# PWM_Isolated.net
KiCad netlist of a schematic drawn in Altium Designer
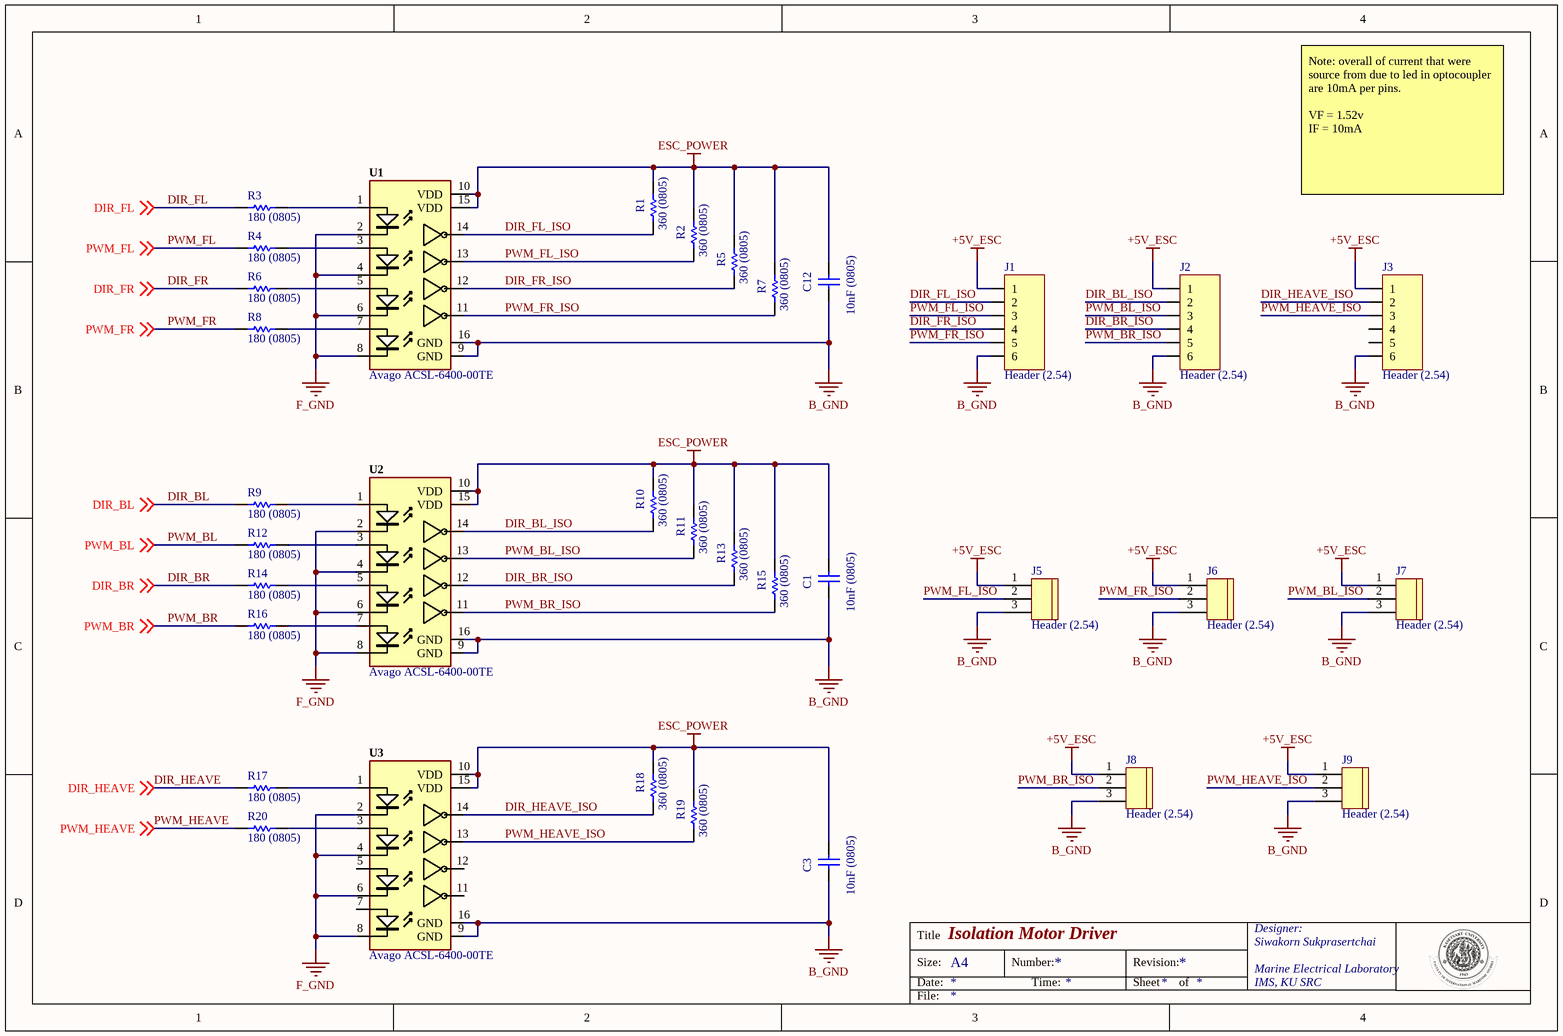
[diagram p0: PWM_Isolated.SchDoc]

(export (version "E")
  (design (tool "Eeschema 10.0.6"))
  (components
    (comp (ref "C1")
      (value "10nF (0805)")
      (footprint "CAPC2013X94X50NL20T25")
      (description "CAP CER 10NF 50V 5% X7R 0805")
      (fields (field (name "MANUFACTURER PART NUMBER") "08055C103JAT2A"))
      (libsource (lib "FavoritesLibrary") (part "CAP-2"))
    )
    (comp (ref "C3")
      (value "10nF (0805)")
      (footprint "CAPC2013X94X50NL20T25")
      (description "CAP CER 10NF 50V 5% X7R 0805")
      (fields (field (name "MANUFACTURER PART NUMBER") "08055C103JAT2A"))
      (libsource (lib "FavoritesLibrary") (part "CAP-2"))
    )
    (comp (ref "C12")
      (value "10nF (0805)")
      (footprint "CAPC2013X94X50NL20T25")
      (description "CAP CER 10NF 50V 5% X7R 0805")
      (fields (field (name "MANUFACTURER PART NUMBER") "08055C103JAT2A"))
      (libsource (lib "FavoritesLibrary") (part "CAP-2"))
    )
    (comp (ref "J1")
      (value "Header (2.54)")
      (footprint "PCB-cqg2o6bffgevoirlg0wu-1")
      (description "Wire-To-Board Connector, Right Angle, AMPMODU Mod II Series, Through Hole, Header, 6, 2.54 mm")
      (fields (field (name "MANUFACTURER PART NUMBER") "826947-6"))
      (libsource (lib "CommunityVault") (part "CMP-c0620b0c5e311fa5-2"))
    )
    (comp (ref "J2")
      (value "Header (2.54)")
      (footprint "PCB-cqg2o6bffgevoirlg0wu-1")
      (description "Wire-To-Board Connector, Right Angle, AMPMODU Mod II Series, Through Hole, Header, 6, 2.54 mm")
      (fields (field (name "MANUFACTURER PART NUMBER") "826947-6"))
      (libsource (lib "CommunityVault") (part "CMP-c0620b0c5e311fa5-2"))
    )
    (comp (ref "J3")
      (value "Header (2.54)")
      (footprint "PCB-cqg2o6bffgevoirlg0wu-1")
      (description "Wire-To-Board Connector, Right Angle, AMPMODU Mod II Series, Through Hole, Header, 6, 2.54 mm")
      (fields (field (name "MANUFACTURER PART NUMBER") "826947-6"))
      (libsource (lib "CommunityVault") (part "CMP-c0620b0c5e311fa5-2"))
    )
    (comp (ref "J5")
      (value "Header (2.54)")
      (footprint "PCB-euxx5fdf5mehbg45u1ir-1")
      (description "Pin strip (standard) MTA-100 Total number of pins 3 TE Connectivity 640455-3 1 pc(s)")
      (fields (field (name "MANUFACTURER PART NUMBER") "640455-3"))
      (libsource (lib "CommunityVault") (part "CMP-b27b7b724c836dbc-1"))
    )
    (comp (ref "J6")
      (value "Header (2.54)")
      (footprint "PCB-euxx5fdf5mehbg45u1ir-1")
      (description "Pin strip (standard) MTA-100 Total number of pins 3 TE Connectivity 640455-3 1 pc(s)")
      (fields (field (name "MANUFACTURER PART NUMBER") "640455-3"))
      (libsource (lib "CommunityVault") (part "CMP-b27b7b724c836dbc-1"))
    )
    (comp (ref "J7")
      (value "Header (2.54)")
      (footprint "PCB-euxx5fdf5mehbg45u1ir-1")
      (description "Pin strip (standard) MTA-100 Total number of pins 3 TE Connectivity 640455-3 1 pc(s)")
      (fields (field (name "MANUFACTURER PART NUMBER") "640455-3"))
      (libsource (lib "CommunityVault") (part "CMP-b27b7b724c836dbc-1"))
    )
    (comp (ref "J8")
      (value "Header (2.54)")
      (footprint "PCB-euxx5fdf5mehbg45u1ir-1")
      (description "Pin strip (standard) MTA-100 Total number of pins 3 TE Connectivity 640455-3 1 pc(s)")
      (fields (field (name "MANUFACTURER PART NUMBER") "640455-3"))
      (libsource (lib "CommunityVault") (part "CMP-b27b7b724c836dbc-1"))
    )
    (comp (ref "J9")
      (value "Header (2.54)")
      (footprint "PCB-euxx5fdf5mehbg45u1ir-1")
      (description "Pin strip (standard) MTA-100 Total number of pins 3 TE Connectivity 640455-3 1 pc(s)")
      (fields (field (name "MANUFACTURER PART NUMBER") "640455-3"))
      (libsource (lib "CommunityVault") (part "CMP-b27b7b724c836dbc-1"))
    )
    (comp (ref "R1")
      (value "360 (0805)")
      (footprint "RESC2013X60X40NL15T20")
      (description "RES SMD 10K OHM 1% 1/3W 0805")
      (libsource (lib "CommunityVault") (part "CMP-1860549-2"))
    )
    (comp (ref "R2")
      (value "360 (0805)")
      (footprint "RESC2013X60X40NL15T20")
      (description "RES SMD 10K OHM 1% 1/3W 0805")
      (libsource (lib "CommunityVault") (part "CMP-1860549-2"))
    )
    (comp (ref "R3")
      (value "180 (0805)")
      (footprint "RESC2013X60X40NL15T20")
      (description "RES SMD 10K OHM 1% 1/3W 0805")
      (libsource (lib "FavoritesLibrary") (part "RES-2"))
    )
    (comp (ref "R4")
      (value "180 (0805)")
      (footprint "RESC2013X60X40NL15T20")
      (description "RES SMD 10K OHM 1% 1/3W 0805")
      (libsource (lib "FavoritesLibrary") (part "RES-2"))
    )
    (comp (ref "R5")
      (value "360 (0805)")
      (footprint "RESC2013X60X40NL15T20")
      (description "RES SMD 10K OHM 1% 1/3W 0805")
      (libsource (lib "CommunityVault") (part "CMP-1860549-2"))
    )
    (comp (ref "R6")
      (value "180 (0805)")
      (footprint "RESC2013X60X40NL15T20")
      (description "RES SMD 10K OHM 1% 1/3W 0805")
      (libsource (lib "FavoritesLibrary") (part "RES-2"))
    )
    (comp (ref "R7")
      (value "360 (0805)")
      (footprint "RESC2013X60X40NL15T20")
      (description "RES SMD 10K OHM 1% 1/3W 0805")
      (libsource (lib "CommunityVault") (part "CMP-1860549-2"))
    )
    (comp (ref "R8")
      (value "180 (0805)")
      (footprint "RESC2013X60X40NL15T20")
      (description "RES SMD 10K OHM 1% 1/3W 0805")
      (libsource (lib "FavoritesLibrary") (part "RES-2"))
    )
    (comp (ref "R9")
      (value "180 (0805)")
      (footprint "RESC2013X60X40NL15T20")
      (description "RES SMD 10K OHM 1% 1/3W 0805")
      (libsource (lib "FavoritesLibrary") (part "RES-2"))
    )
    (comp (ref "R10")
      (value "360 (0805)")
      (footprint "RESC2013X60X40NL15T20")
      (description "RES SMD 10K OHM 1% 1/3W 0805")
      (libsource (lib "CommunityVault") (part "CMP-1860549-2"))
    )
    (comp (ref "R11")
      (value "360 (0805)")
      (footprint "RESC2013X60X40NL15T20")
      (description "RES SMD 10K OHM 1% 1/3W 0805")
      (libsource (lib "CommunityVault") (part "CMP-1860549-2"))
    )
    (comp (ref "R12")
      (value "180 (0805)")
      (footprint "RESC2013X60X40NL15T20")
      (description "RES SMD 10K OHM 1% 1/3W 0805")
      (libsource (lib "FavoritesLibrary") (part "RES-2"))
    )
    (comp (ref "R13")
      (value "360 (0805)")
      (footprint "RESC2013X60X40NL15T20")
      (description "RES SMD 10K OHM 1% 1/3W 0805")
      (libsource (lib "CommunityVault") (part "CMP-1860549-2"))
    )
    (comp (ref "R14")
      (value "180 (0805)")
      (footprint "RESC2013X60X40NL15T20")
      (description "RES SMD 10K OHM 1% 1/3W 0805")
      (libsource (lib "FavoritesLibrary") (part "RES-2"))
    )
    (comp (ref "R15")
      (value "360 (0805)")
      (footprint "RESC2013X60X40NL15T20")
      (description "RES SMD 10K OHM 1% 1/3W 0805")
      (libsource (lib "CommunityVault") (part "CMP-1860549-2"))
    )
    (comp (ref "R16")
      (value "180 (0805)")
      (footprint "RESC2013X60X40NL15T20")
      (description "RES SMD 10K OHM 1% 1/3W 0805")
      (libsource (lib "FavoritesLibrary") (part "RES-2"))
    )
    (comp (ref "R17")
      (value "180 (0805)")
      (footprint "RESC2013X60X40NL15T20")
      (description "RES SMD 10K OHM 1% 1/3W 0805")
      (libsource (lib "FavoritesLibrary") (part "RES-2"))
    )
    (comp (ref "R18")
      (value "360 (0805)")
      (footprint "RESC2013X60X40NL15T20")
      (description "RES SMD 10K OHM 1% 1/3W 0805")
      (libsource (lib "CommunityVault") (part "CMP-1860549-2"))
    )
    (comp (ref "R19")
      (value "360 (0805)")
      (footprint "RESC2013X60X40NL15T20")
      (description "RES SMD 10K OHM 1% 1/3W 0805")
      (libsource (lib "CommunityVault") (part "CMP-1860549-2"))
    )
    (comp (ref "R20")
      (value "180 (0805)")
      (footprint "RESC2013X60X40NL15T20")
      (description "RES SMD 10K OHM 1% 1/3W 0805")
      (libsource (lib "FavoritesLibrary") (part "RES-2"))
    )
    (comp (ref "U1")
      (value "Avago ACSL-6400-00TE")
      (footprint "PCB-bbpchabnk3r0s5lan1zs-1")
      (description "Multi-Channel and Bi-Directional, 15 MBd (typ) Digital Logic Gate Optocoupler")
      (fields (field (name "MANUFACTURER PART NUMBER") "ACSL-6400-00TE"))
      (libsource (lib "FavoritesLibrary") (part "SYM-6f44a640fcefb083-1"))
    )
    (comp (ref "U2")
      (value "Avago ACSL-6400-00TE")
      (footprint "PCB-bbpchabnk3r0s5lan1zs-1")
      (description "Multi-Channel and Bi-Directional, 15 MBd (typ) Digital Logic Gate Optocoupler")
      (fields (field (name "MANUFACTURER PART NUMBER") "ACSL-6400-00TE"))
      (libsource (lib "FavoritesLibrary") (part "SYM-6f44a640fcefb083-1"))
    )
    (comp (ref "U3")
      (value "Avago ACSL-6400-00TE")
      (footprint "PCB-bbpchabnk3r0s5lan1zs-1")
      (description "Multi-Channel and Bi-Directional, 15 MBd (typ) Digital Logic Gate Optocoupler")
      (fields (field (name "MANUFACTURER PART NUMBER") "ACSL-6400-00TE"))
      (libsource (lib "FavoritesLibrary") (part "SYM-6f44a640fcefb083-1"))
    )
  )
  (nets
    (net (code "1") (name "+5V_ESC") (class "Default")
      (node (ref "J1") (pin "1") (pinfunction "1_1") (pintype "passive"))
      (node (ref "J2") (pin "1") (pinfunction "1_1") (pintype "passive"))
      (node (ref "J3") (pin "1") (pinfunction "1_1") (pintype "passive"))
      (node (ref "J5") (pin "1") (pinfunction "1_1") (pintype "passive"))
      (node (ref "J6") (pin "1") (pinfunction "1_1") (pintype "passive"))
      (node (ref "J7") (pin "1") (pinfunction "1_1") (pintype "passive"))
      (node (ref "J8") (pin "1") (pinfunction "1_1") (pintype "passive"))
      (node (ref "J9") (pin "1") (pinfunction "1_1") (pintype "passive"))
    )
    (net (code "2") (name "/DIR_BL_ISO") (class "Default")
      (node (ref "J2") (pin "2") (pinfunction "2_2") (pintype "passive"))
      (node (ref "R10") (pin "2") (pinfunction "2_2") (pintype "passive"))
      (node (ref "U2") (pin "14") (pinfunction "14_14") (pintype "passive"))
    )
    (net (code "3") (name "/DIR_BR_ISO") (class "Default")
      (node (ref "J2") (pin "4") (pinfunction "4_4") (pintype "passive"))
      (node (ref "R13") (pin "2") (pinfunction "2_2") (pintype "passive"))
      (node (ref "U2") (pin "12") (pinfunction "12_12") (pintype "passive"))
    )
    (net (code "4") (name "/DIR_FL_ISO") (class "Default")
      (node (ref "J1") (pin "2") (pinfunction "2_2") (pintype "passive"))
      (node (ref "R1") (pin "2") (pinfunction "2_2") (pintype "passive"))
      (node (ref "U1") (pin "14") (pinfunction "14_14") (pintype "passive"))
    )
    (net (code "5") (name "/DIR_FR_ISO") (class "Default")
      (node (ref "J1") (pin "4") (pinfunction "4_4") (pintype "passive"))
      (node (ref "R5") (pin "2") (pinfunction "2_2") (pintype "passive"))
      (node (ref "U1") (pin "12") (pinfunction "12_12") (pintype "passive"))
    )
    (net (code "6") (name "/DIR_HEAVE_ISO") (class "Default")
      (node (ref "J3") (pin "2") (pinfunction "2_2") (pintype "passive"))
      (node (ref "R18") (pin "2") (pinfunction "2_2") (pintype "passive"))
      (node (ref "U3") (pin "14") (pinfunction "14_14") (pintype "passive"))
    )
    (net (code "7") (name "/PWM_BL_ISO") (class "Default")
      (node (ref "J2") (pin "3") (pinfunction "3_3") (pintype "passive"))
      (node (ref "J7") (pin "2") (pinfunction "2_2") (pintype "passive"))
      (node (ref "R11") (pin "2") (pinfunction "2_2") (pintype "passive"))
      (node (ref "U2") (pin "13") (pinfunction "13_13") (pintype "passive"))
    )
    (net (code "8") (name "/PWM_BR_ISO") (class "Default")
      (node (ref "J2") (pin "5") (pinfunction "5_5") (pintype "passive"))
      (node (ref "J8") (pin "2") (pinfunction "2_2") (pintype "passive"))
      (node (ref "R15") (pin "2") (pinfunction "2_2") (pintype "passive"))
      (node (ref "U2") (pin "11") (pinfunction "11_11") (pintype "passive"))
    )
    (net (code "9") (name "/PWM_FL_ISO") (class "Default")
      (node (ref "J1") (pin "3") (pinfunction "3_3") (pintype "passive"))
      (node (ref "J5") (pin "2") (pinfunction "2_2") (pintype "passive"))
      (node (ref "R2") (pin "2") (pinfunction "2_2") (pintype "passive"))
      (node (ref "U1") (pin "13") (pinfunction "13_13") (pintype "passive"))
    )
    (net (code "10") (name "/PWM_FR_ISO") (class "Default")
      (node (ref "J1") (pin "5") (pinfunction "5_5") (pintype "passive"))
      (node (ref "J6") (pin "2") (pinfunction "2_2") (pintype "passive"))
      (node (ref "R7") (pin "2") (pinfunction "2_2") (pintype "passive"))
      (node (ref "U1") (pin "11") (pinfunction "11_11") (pintype "passive"))
    )
    (net (code "11") (name "/PWM_HEAVE_ISO") (class "Default")
      (node (ref "J3") (pin "3") (pinfunction "3_3") (pintype "passive"))
      (node (ref "J9") (pin "2") (pinfunction "2_2") (pintype "passive"))
      (node (ref "R19") (pin "2") (pinfunction "2_2") (pintype "passive"))
      (node (ref "U3") (pin "13") (pinfunction "13_13") (pintype "passive"))
    )
    (net (code "12") (name "B_GND") (class "Default")
      (node (ref "C1") (pin "1") (pinfunction "1_1") (pintype "passive"))
      (node (ref "C12") (pin "1") (pinfunction "1_1") (pintype "passive"))
      (node (ref "C3") (pin "1") (pinfunction "1_1") (pintype "passive"))
      (node (ref "J1") (pin "6") (pinfunction "6_6") (pintype "passive"))
      (node (ref "J2") (pin "6") (pinfunction "6_6") (pintype "passive"))
      (node (ref "J3") (pin "6") (pinfunction "6_6") (pintype "passive"))
      (node (ref "J5") (pin "3") (pinfunction "3_3") (pintype "passive"))
      (node (ref "J6") (pin "3") (pinfunction "3_3") (pintype "passive"))
      (node (ref "J7") (pin "3") (pinfunction "3_3") (pintype "passive"))
      (node (ref "J8") (pin "3") (pinfunction "3_3") (pintype "passive"))
      (node (ref "J9") (pin "3") (pinfunction "3_3") (pintype "passive"))
      (node (ref "U1") (pin "16") (pinfunction "GND_16") (pintype "passive"))
      (node (ref "U1") (pin "9") (pinfunction "GND_9") (pintype "passive"))
      (node (ref "U2") (pin "16") (pinfunction "GND_16") (pintype "passive"))
      (node (ref "U2") (pin "9") (pinfunction "GND_9") (pintype "passive"))
      (node (ref "U3") (pin "16") (pinfunction "GND_16") (pintype "passive"))
      (node (ref "U3") (pin "9") (pinfunction "GND_9") (pintype "passive"))
    )
    (net (code "13") (name "DIR_BL") (class "Default")
      (node (ref "R9") (pin "2") (pinfunction "2_2") (pintype "passive"))
    )
    (net (code "14") (name "DIR_BR") (class "Default")
      (node (ref "R14") (pin "2") (pinfunction "2_2") (pintype "passive"))
    )
    (net (code "15") (name "DIR_FL") (class "Default")
      (node (ref "R3") (pin "2") (pinfunction "2_2") (pintype "passive"))
    )
    (net (code "16") (name "DIR_FR") (class "Default")
      (node (ref "R6") (pin "2") (pinfunction "2_2") (pintype "passive"))
    )
    (net (code "17") (name "DIR_HEAVE") (class "Default")
      (node (ref "R17") (pin "2") (pinfunction "2_2") (pintype "passive"))
    )
    (net (code "18") (name "ESC_POWER") (class "Default")
      (node (ref "C1") (pin "2") (pinfunction "2_2") (pintype "passive"))
      (node (ref "C12") (pin "2") (pinfunction "2_2") (pintype "passive"))
      (node (ref "C3") (pin "2") (pinfunction "2_2") (pintype "passive"))
      (node (ref "R1") (pin "1") (pinfunction "1_1") (pintype "passive"))
      (node (ref "R10") (pin "1") (pinfunction "1_1") (pintype "passive"))
      (node (ref "R11") (pin "1") (pinfunction "1_1") (pintype "passive"))
      (node (ref "R13") (pin "1") (pinfunction "1_1") (pintype "passive"))
      (node (ref "R15") (pin "1") (pinfunction "1_1") (pintype "passive"))
      (node (ref "R18") (pin "1") (pinfunction "1_1") (pintype "passive"))
      (node (ref "R19") (pin "1") (pinfunction "1_1") (pintype "passive"))
      (node (ref "R2") (pin "1") (pinfunction "1_1") (pintype "passive"))
      (node (ref "R5") (pin "1") (pinfunction "1_1") (pintype "passive"))
      (node (ref "R7") (pin "1") (pinfunction "1_1") (pintype "passive"))
      (node (ref "U1") (pin "10") (pinfunction "VDD_10") (pintype "passive"))
      (node (ref "U1") (pin "15") (pinfunction "VDD_15") (pintype "passive"))
      (node (ref "U2") (pin "10") (pinfunction "VDD_10") (pintype "passive"))
      (node (ref "U2") (pin "15") (pinfunction "VDD_15") (pintype "passive"))
      (node (ref "U3") (pin "10") (pinfunction "VDD_10") (pintype "passive"))
      (node (ref "U3") (pin "15") (pinfunction "VDD_15") (pintype "passive"))
    )
    (net (code "19") (name "F_GND") (class "Default")
      (node (ref "U1") (pin "2") (pinfunction "2_2") (pintype "passive"))
      (node (ref "U1") (pin "4") (pinfunction "4_4") (pintype "passive"))
      (node (ref "U1") (pin "6") (pinfunction "6_6") (pintype "passive"))
      (node (ref "U1") (pin "8") (pinfunction "8_8") (pintype "passive"))
      (node (ref "U2") (pin "2") (pinfunction "2_2") (pintype "passive"))
      (node (ref "U2") (pin "4") (pinfunction "4_4") (pintype "passive"))
      (node (ref "U2") (pin "6") (pinfunction "6_6") (pintype "passive"))
      (node (ref "U2") (pin "8") (pinfunction "8_8") (pintype "passive"))
      (node (ref "U3") (pin "2") (pinfunction "2_2") (pintype "passive"))
      (node (ref "U3") (pin "4") (pinfunction "4_4") (pintype "passive"))
      (node (ref "U3") (pin "6") (pinfunction "6_6") (pintype "passive"))
      (node (ref "U3") (pin "8") (pinfunction "8_8") (pintype "passive"))
    )
    (net (code "20") (name "Net-(R3-Pad1)") (class "Default")
      (node (ref "R3") (pin "1") (pinfunction "1_1") (pintype "passive"))
      (node (ref "U1") (pin "1") (pinfunction "1_1") (pintype "passive"))
    )
    (net (code "21") (name "Net-(R4-Pad1)") (class "Default")
      (node (ref "R4") (pin "1") (pinfunction "1_1") (pintype "passive"))
      (node (ref "U1") (pin "3") (pinfunction "3_3") (pintype "passive"))
    )
    (net (code "22") (name "Net-(R6-Pad1)") (class "Default")
      (node (ref "R6") (pin "1") (pinfunction "1_1") (pintype "passive"))
      (node (ref "U1") (pin "5") (pinfunction "5_5") (pintype "passive"))
    )
    (net (code "23") (name "Net-(R8-Pad1)") (class "Default")
      (node (ref "R8") (pin "1") (pinfunction "1_1") (pintype "passive"))
      (node (ref "U1") (pin "7") (pinfunction "7_7") (pintype "passive"))
    )
    (net (code "24") (name "Net-(R9-Pad1)") (class "Default")
      (node (ref "R9") (pin "1") (pinfunction "1_1") (pintype "passive"))
      (node (ref "U2") (pin "1") (pinfunction "1_1") (pintype "passive"))
    )
    (net (code "25") (name "Net-(R12-Pad1)") (class "Default")
      (node (ref "R12") (pin "1") (pinfunction "1_1") (pintype "passive"))
      (node (ref "U2") (pin "3") (pinfunction "3_3") (pintype "passive"))
    )
    (net (code "26") (name "Net-(R14-Pad1)") (class "Default")
      (node (ref "R14") (pin "1") (pinfunction "1_1") (pintype "passive"))
      (node (ref "U2") (pin "5") (pinfunction "5_5") (pintype "passive"))
    )
    (net (code "27") (name "Net-(R16-Pad1)") (class "Default")
      (node (ref "R16") (pin "1") (pinfunction "1_1") (pintype "passive"))
      (node (ref "U2") (pin "7") (pinfunction "7_7") (pintype "passive"))
    )
    (net (code "28") (name "Net-(R17-Pad1)") (class "Default")
      (node (ref "R17") (pin "1") (pinfunction "1_1") (pintype "passive"))
      (node (ref "U3") (pin "1") (pinfunction "1_1") (pintype "passive"))
    )
    (net (code "29") (name "Net-(R20-Pad1)") (class "Default")
      (node (ref "R20") (pin "1") (pinfunction "1_1") (pintype "passive"))
      (node (ref "U3") (pin "3") (pinfunction "3_3") (pintype "passive"))
    )
    (net (code "30") (name "PWM_BL") (class "Default")
      (node (ref "R12") (pin "2") (pinfunction "2_2") (pintype "passive"))
    )
    (net (code "31") (name "PWM_BR") (class "Default")
      (node (ref "R16") (pin "2") (pinfunction "2_2") (pintype "passive"))
    )
    (net (code "32") (name "PWM_FL") (class "Default")
      (node (ref "R4") (pin "2") (pinfunction "2_2") (pintype "passive"))
    )
    (net (code "33") (name "PWM_FR") (class "Default")
      (node (ref "R8") (pin "2") (pinfunction "2_2") (pintype "passive"))
    )
    (net (code "34") (name "PWM_HEAVE") (class "Default")
      (node (ref "R20") (pin "2") (pinfunction "2_2") (pintype "passive"))
    )
    (net (code "35") (name "unconnected-(J3-Pad4)") (class "Default")
      (node (ref "J3") (pin "4") (pinfunction "4_4") (pintype "passive"))
    )
    (net (code "36") (name "unconnected-(J3-Pad5)") (class "Default")
      (node (ref "J3") (pin "5") (pinfunction "5_5") (pintype "passive"))
    )
    (net (code "37") (name "unconnected-(U3-Pad5)") (class "Default")
      (node (ref "U3") (pin "5") (pinfunction "5_5") (pintype "passive"))
    )
    (net (code "38") (name "unconnected-(U3-Pad7)") (class "Default")
      (node (ref "U3") (pin "7") (pinfunction "7_7") (pintype "passive"))
    )
    (net (code "39") (name "unconnected-(U3-Pad11)") (class "Default")
      (node (ref "U3") (pin "11") (pinfunction "11_11") (pintype "passive"))
    )
    (net (code "40") (name "unconnected-(U3-Pad12)") (class "Default")
      (node (ref "U3") (pin "12") (pinfunction "12_12") (pintype "passive"))
    )
  )
)
